# ADC.net
KiCad netlist of a schematic drawn in Altium Designer
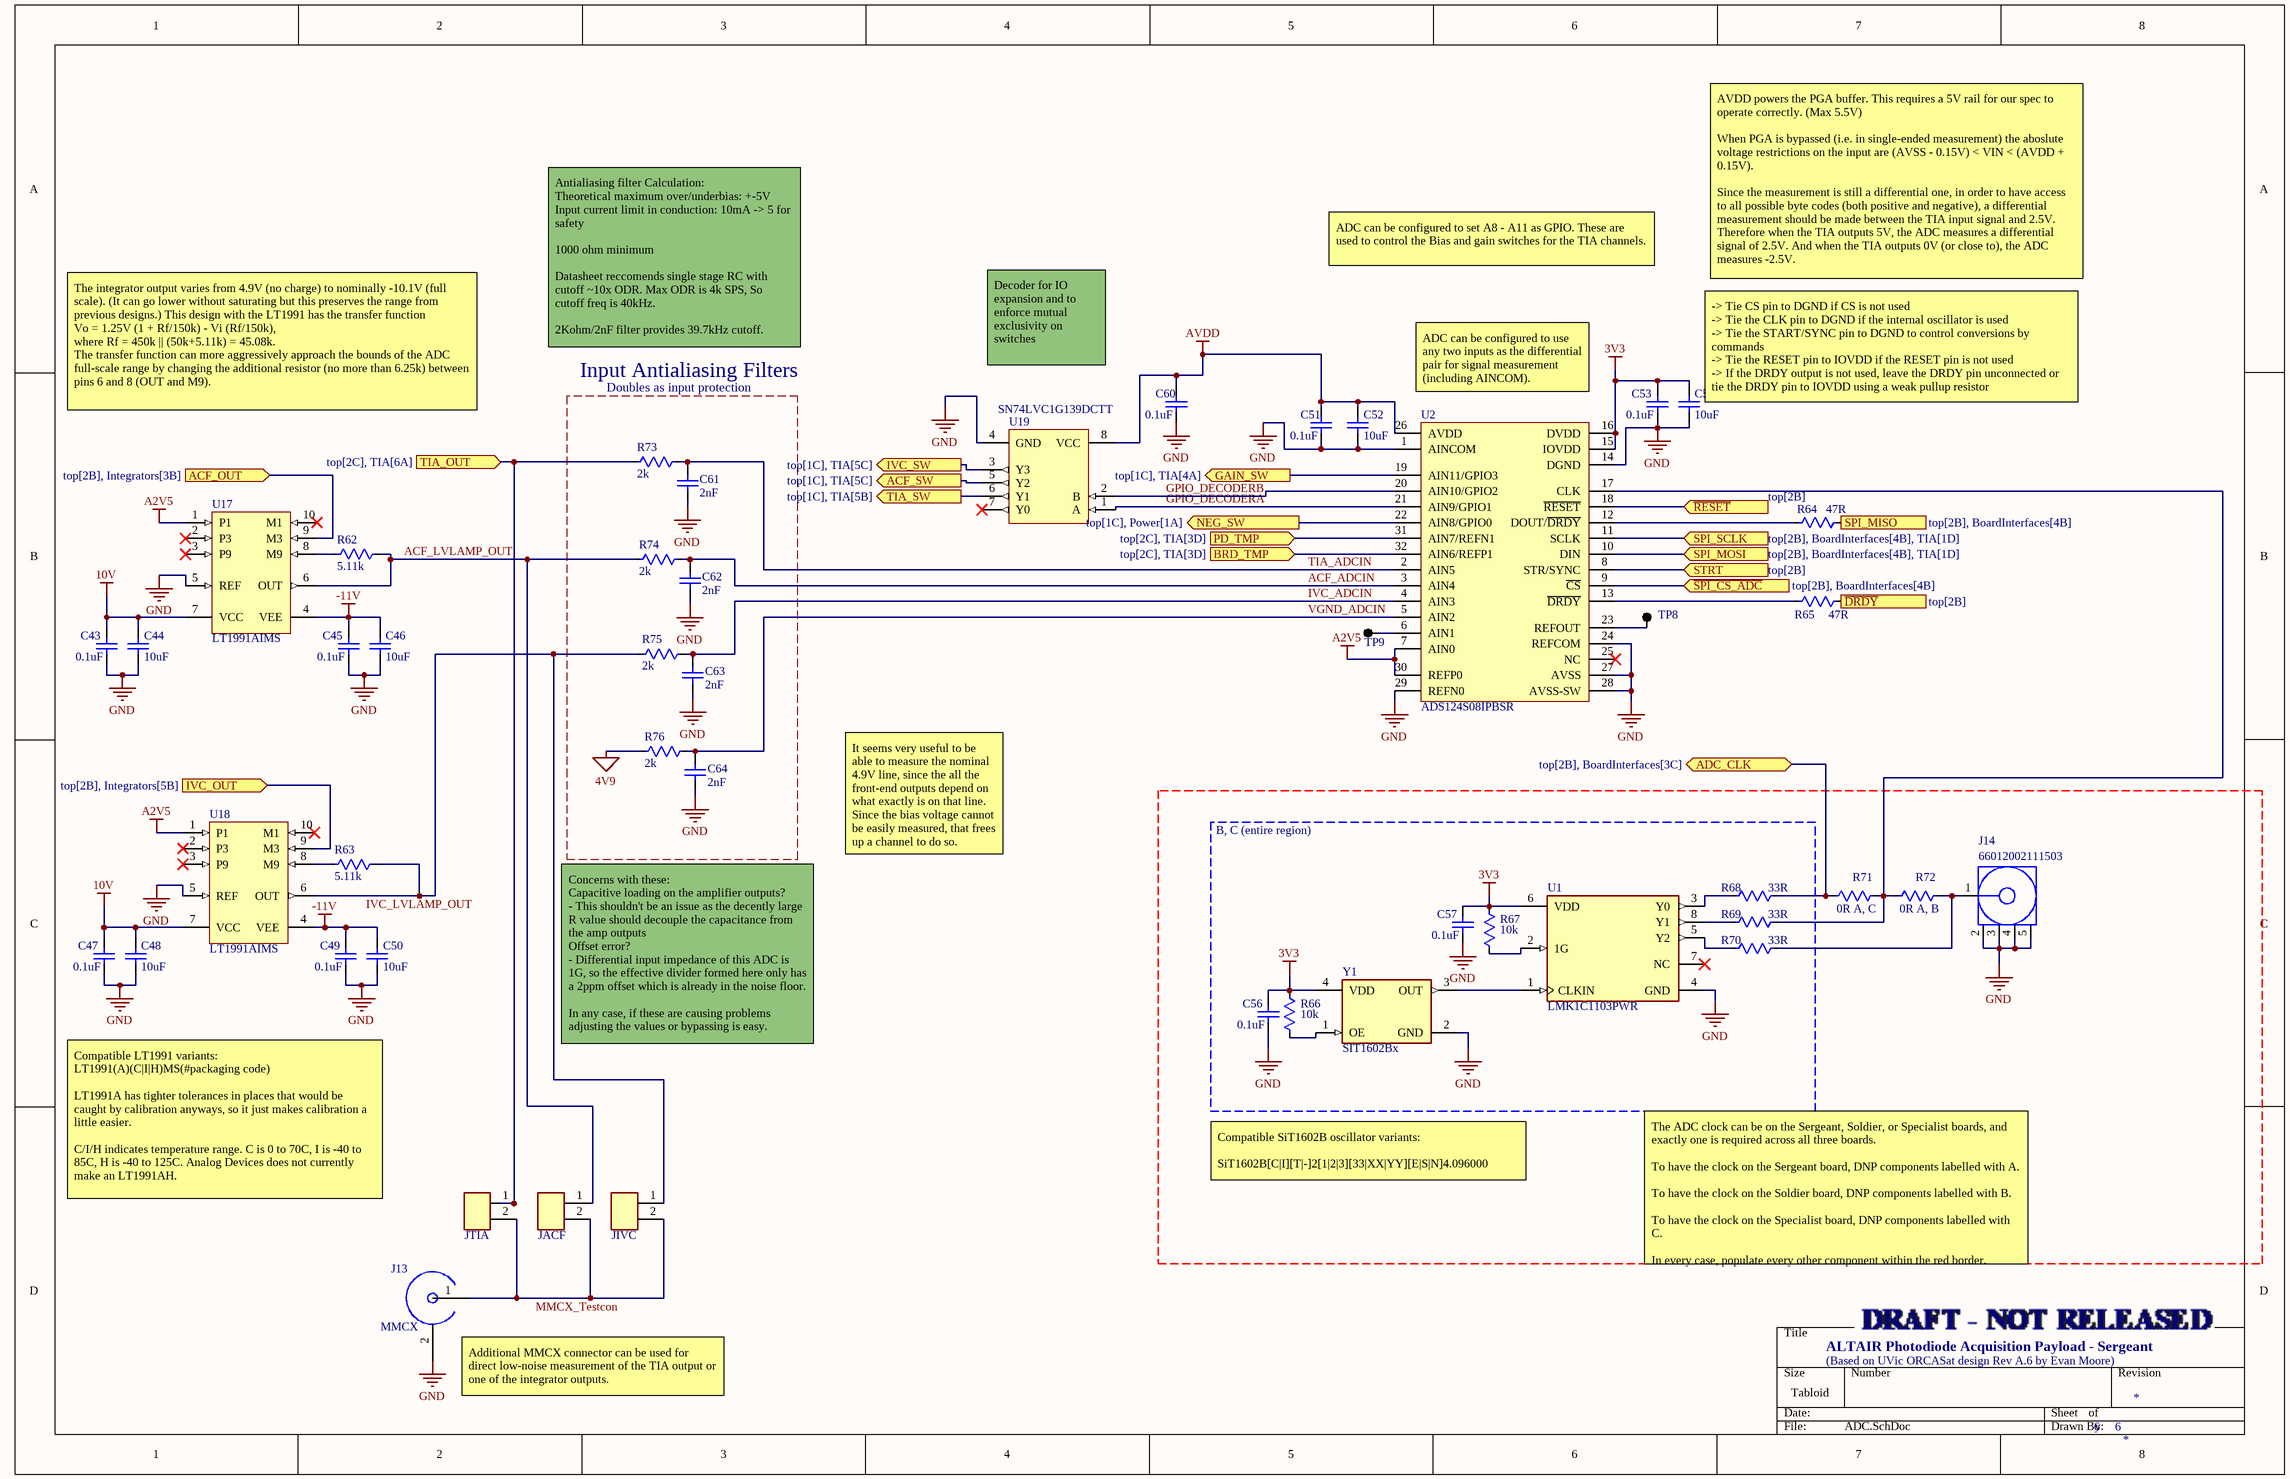
[diagram p0: ADC.SchDoc]

(export (version "E")
  (design (tool "Eeschema 10.0.6"))
  (components
    (comp (ref "C43")
      (value "0.1uF")
      (footprint "CAP 0603 NON-IPC KEMET X7R")
      (description "Kemet C0603C104K5RACAUTO - Cap Ceramic 0.1uF 50V X7R 10% 0603 125C Paper T/R")
      (fields (field (name "MF") "Kemet") (field (name "MP") "C0603C104K5RACAUTO"))
      (libsource (lib "ALTAIR_PD_Capacitors") (part "CAP"))
    )
    (comp (ref "C44")
      (value "10uF")
      (footprint "CAP 0805 IPC MID DENSITY")
      (description "Murata GRM21BR61E106KA73L - Cap Ceramic 10uF 10% 25V X5R 0805")
      (fields (field (name "MF") "Murata") (field (name "MP") "GRM21BR61E106KA73L"))
      (libsource (lib "ALTAIR_PD_Capacitors") (part "CAP"))
    )
    (comp (ref "C45")
      (value "0.1uF")
      (footprint "CAP 0603 NON-IPC KEMET X7R")
      (description "Kemet C0603C104K5RACAUTO - Cap Ceramic 0.1uF 50V X7R 10% 0603 125C Paper T/R")
      (fields (field (name "MF") "Kemet") (field (name "MP") "C0603C104K5RACAUTO"))
      (libsource (lib "ALTAIR_PD_Capacitors") (part "CAP"))
    )
    (comp (ref "C46")
      (value "10uF")
      (footprint "CAP 0805 IPC MID DENSITY")
      (description "Murata GRM21BR61E106KA73L - Cap Ceramic 10uF 10% 25V X5R 0805")
      (fields (field (name "MF") "Murata") (field (name "MP") "GRM21BR61E106KA73L"))
      (libsource (lib "ALTAIR_PD_Capacitors") (part "CAP"))
    )
    (comp (ref "C47")
      (value "0.1uF")
      (footprint "CAP 0603 NON-IPC KEMET X7R")
      (description "Kemet C0603C104K5RACAUTO - Cap Ceramic 0.1uF 50V X7R 10% 0603 125C Paper T/R")
      (fields (field (name "MF") "Kemet") (field (name "MP") "C0603C104K5RACAUTO"))
      (libsource (lib "ALTAIR_PD_Capacitors") (part "CAP"))
    )
    (comp (ref "C48")
      (value "10uF")
      (footprint "CAP 0805 IPC MID DENSITY")
      (description "Murata GRM21BR61E106KA73L - Cap Ceramic 10uF 10% 25V X5R 0805")
      (fields (field (name "MF") "Murata") (field (name "MP") "GRM21BR61E106KA73L"))
      (libsource (lib "ALTAIR_PD_Capacitors") (part "CAP"))
    )
    (comp (ref "C49")
      (value "0.1uF")
      (footprint "CAP 0603 NON-IPC KEMET X7R")
      (description "Kemet C0603C104K5RACAUTO - Cap Ceramic 0.1uF 50V X7R 10% 0603 125C Paper T/R")
      (fields (field (name "MF") "Kemet") (field (name "MP") "C0603C104K5RACAUTO"))
      (libsource (lib "ALTAIR_PD_Capacitors") (part "CAP"))
    )
    (comp (ref "C50")
      (value "10uF")
      (footprint "CAP 0805 IPC MID DENSITY")
      (description "Murata GRM21BR61E106KA73L - Cap Ceramic 10uF 10% 25V X5R 0805")
      (fields (field (name "MF") "Murata") (field (name "MP") "GRM21BR61E106KA73L"))
      (libsource (lib "ALTAIR_PD_Capacitors") (part "CAP"))
    )
    (comp (ref "C51")
      (value "0.1uF")
      (footprint "CAP 0603 IPC MID DENSITY")
      (description "Kemet C0603C104K5RACAUTO - Cap Ceramic 0.1uF 50V X7R 10% 0603 125C Paper T/R")
      (fields (field (name "MF") "Kemet") (field (name "MP") "C0603C104K5RACAUTO"))
      (libsource (lib "ALTAIR_PD_Capacitors") (part "CAP"))
    )
    (comp (ref "C52")
      (value "10uF")
      (footprint "CAP 0805 IPC MID DENSITY")
      (description "Murata GRM21BR61E106KA73L - Cap Ceramic 10uF 10% 25V X5R 0805")
      (fields (field (name "MF") "Murata") (field (name "MP") "GRM21BR61E106KA73L"))
      (libsource (lib "ALTAIR_PD_Capacitors") (part "CAP"))
    )
    (comp (ref "C53")
      (value "0.1uF")
      (footprint "CAP 0603 IPC MID DENSITY")
      (description "Kemet C0603C104K5RACAUTO - Cap Ceramic 0.1uF 50V X7R 10% 0603 125C Paper T/R")
      (fields (field (name "MF") "Kemet") (field (name "MP") "C0603C104K5RACAUTO"))
      (libsource (lib "ALTAIR_PD_Capacitors") (part "CAP"))
    )
    (comp (ref "C54")
      (value "10uF")
      (footprint "CAP 0805 IPC MID DENSITY")
      (description "Murata GRM21BR61E106KA73L - Cap Ceramic 10uF 10% 25V X5R 0805")
      (fields (field (name "MF") "Murata") (field (name "MP") "GRM21BR61E106KA73L"))
      (libsource (lib "ALTAIR_PD_Capacitors") (part "CAP"))
    )
    (comp (ref "C56")
      (value "0.1uF")
      (footprint "CAP 0603 IPC MID DENSITY")
      (description "Kemet C0603C104K5RACAUTO - Cap Ceramic 0.1uF 50V X7R 10% 0603 125C Paper T/R")
      (fields (field (name "MF") "Kemet") (field (name "MP") "C0603C104K5RACAUTO"))
      (libsource (lib "ALTAIR_PD_Capacitors") (part "CAP"))
    )
    (comp (ref "C57")
      (value "0.1uF")
      (footprint "CAP 0603 IPC MID DENSITY")
      (description "Kemet C0603C104K5RACAUTO - Cap Ceramic 0.1uF 50V X7R 10% 0603 125C Paper T/R")
      (fields (field (name "MF") "Kemet") (field (name "MP") "C0603C104K5RACAUTO"))
      (libsource (lib "ALTAIR_PD_Capacitors") (part "CAP"))
    )
    (comp (ref "C60")
      (value "0.1uF")
      (footprint "CAP 0603 IPC MID DENSITY")
      (description "Kemet C0603C104K5RACAUTO - Cap Ceramic 0.1uF 50V X7R 10% 0603 125C Paper T/R")
      (fields (field (name "MF") "Kemet") (field (name "MP") "C0603C104K5RACAUTO"))
      (libsource (lib "ALTAIR_PD_Capacitors") (part "CAP"))
    )
    (comp (ref "C61")
      (value "2nF")
      (footprint "CAP 0603 IPC MID DENSITY")
      (description "Cap, Nonpolar, Any, Must choose footprint manually")
      (libsource (lib "ALTAIR_PD_Capacitors") (part "CAP"))
    )
    (comp (ref "C62")
      (value "2nF")
      (footprint "CAP 0603 IPC MID DENSITY")
      (description "Cap, Nonpolar, Any, Must choose footprint manually")
      (libsource (lib "ALTAIR_PD_Capacitors") (part "CAP"))
    )
    (comp (ref "C63")
      (value "2nF")
      (footprint "CAP 0603 IPC MID DENSITY")
      (description "Cap, Nonpolar, Any, Must choose footprint manually")
      (libsource (lib "ALTAIR_PD_Capacitors") (part "CAP"))
    )
    (comp (ref "C64")
      (value "2nF")
      (footprint "CAP 0603 IPC MID DENSITY")
      (description "Cap, Nonpolar, Any, Must choose footprint manually")
      (libsource (lib "ALTAIR_PD_Capacitors") (part "CAP"))
    )
    (comp (ref "J13")
      (value "MMCX")
      (footprint "COAX MMCX SMD")
      (description "Conn MMCX F 50Ohm Solder ST SMD Gold Tray")
      (fields (field (name "MF") "Molex") (field (name "MP") "0734152061"))
      (libsource (lib "ALTAIR_PD_Coaxial") (part "MMCX_recp"))
    )
    (comp (ref "J14")
      (value "66012002111503")
      (footprint "COAX MMCX THT")
      (description "Rf Coaxial, Mmcx Jack, 50 Ohm, Pcb Rohs Compliant: Yes ¦Wurth Elektronik 66012002111503")
      (fields (field (name "MF") "Wurth Elektronik"))
      (libsource (lib "ALTAIR_PD_Coaxial") (part "CMP-207975-000001-3"))
    )
    (comp (ref "JACF")
      (value "JACF")
      (footprint "ALTAIR_PD_Headers:JUMPER 2POS 1MM PITCH THT")
      (description "2x1 Header THT 1mm Pitch")
      (fields
        (field (name "MF") "GCT (GLOBAL CONNECTOR TECHNOLOGY)")
        (field (name "MP") "BC020-02-A-0200-0300-L-G")
      )
      (libsource (lib "ALTAIR_PD_Headers") (part "BC020-02-A-0200-0300-L-G"))
    )
    (comp (ref "JIVC")
      (value "JIVC")
      (footprint "ALTAIR_PD_Headers:JUMPER 2POS 1MM PITCH THT")
      (description "2x1 Header THT 1mm Pitch")
      (fields
        (field (name "MF") "GCT (GLOBAL CONNECTOR TECHNOLOGY)")
        (field (name "MP") "BC020-02-A-0200-0300-L-G")
      )
      (libsource (lib "ALTAIR_PD_Headers") (part "BC020-02-A-0200-0300-L-G"))
    )
    (comp (ref "JTIA")
      (value "JTIA")
      (footprint "ALTAIR_PD_Headers:JUMPER 2POS 1MM PITCH THT")
      (description "2x1 Header THT 1mm Pitch")
      (fields
        (field (name "MF") "GCT (GLOBAL CONNECTOR TECHNOLOGY)")
        (field (name "MP") "BC020-02-A-0200-0300-L-G")
      )
      (libsource (lib "ALTAIR_PD_Headers") (part "BC020-02-A-0200-0300-L-G"))
    )
    (comp (ref "R62")
      (value "5.11k")
      (footprint "RES 0402 IPC MID DENSITY")
      (description "Panasonic ERA-2AEB5111X - Res 5.11k 0.1% 1/16W SMD 0402")
      (fields (field (name "MF") "Panasonic Electronic Components") (field (name "MP") "ERA-2AEB5111X"))
      (libsource (lib "ALTAIR_PD_Resistors") (part "RES"))
    )
    (comp (ref "R63")
      (value "5.11k")
      (footprint "RES 0402 IPC MID DENSITY")
      (description "Panasonic ERA-2AEB5111X - Res 5.11k 0.1% 1/16W SMD 0402")
      (fields (field (name "MF") "Panasonic Electronic Components") (field (name "MP") "ERA-2AEB5111X"))
      (libsource (lib "ALTAIR_PD_Resistors") (part "RES"))
    )
    (comp (ref "R64")
      (value "47R")
      (footprint "RES 0402 NON-IPC SEI")
      (description "Stackpole RMCF0402JT47R0 - Res 47Ohm 5% 0.063W 0402 Thick Film AEC-Q200 compliant")
      (fields (field (name "MF") "Stackpole Electronics Inc.") (field (name "MP") "RMCF0402JT47R0"))
      (libsource (lib "ALTAIR_PD_Resistors") (part "RES"))
    )
    (comp (ref "R65")
      (value "47R")
      (footprint "RES 0402 NON-IPC SEI")
      (description "Stackpole RMCF0402JT47R0 - Res 47Ohm 5% 0.063W 0402 Thick Film AEC-Q200 compliant")
      (fields (field (name "MF") "Stackpole Electronics Inc.") (field (name "MP") "RMCF0402JT47R0"))
      (libsource (lib "ALTAIR_PD_Resistors") (part "RES"))
    )
    (comp (ref "R66")
      (value "10k")
      (footprint "RES 0603 IPC MID DENSITY")
      (description "Vishay CRCW060310K0FKEA SMD 0603 10k, CRCW e3 Series, 75V, thick film, 100mW")
      (fields (field (name "MF") "Vishay Dale") (field (name "MP") "CRCW060310K0FKEA"))
      (libsource (lib "ALTAIR_PD_Resistors") (part "RES"))
    )
    (comp (ref "R67")
      (value "10k")
      (footprint "RES 0603 IPC MID DENSITY")
      (description "Vishay CRCW060310K0FKEA SMD 0603 10k, CRCW e3 Series, 75V, thick film, 100mW")
      (fields (field (name "MF") "Vishay Dale") (field (name "MP") "CRCW060310K0FKEA"))
      (libsource (lib "ALTAIR_PD_Resistors") (part "RES"))
    )
    (comp (ref "R68")
      (value "33R")
      (footprint "RES 0402 NON-IPC YAGEO")
      (description "Yageo RC0402FR-0733RL - Res 33Ohm 1% 1/16W 0402")
      (fields (field (name "MF") "YAGEO") (field (name "MP") "RC0402FR-0733RL"))
      (libsource (lib "ALTAIR_PD_Resistors") (part "RES"))
    )
    (comp (ref "R69")
      (value "33R")
      (footprint "RES 0402 NON-IPC YAGEO")
      (description "Yageo RC0402FR-0733RL - Res 33Ohm 1% 1/16W 0402")
      (fields (field (name "MF") "YAGEO") (field (name "MP") "RC0402FR-0733RL"))
      (libsource (lib "ALTAIR_PD_Resistors") (part "RES"))
    )
    (comp (ref "R70")
      (value "33R")
      (footprint "RES 0402 NON-IPC YAGEO")
      (description "Yageo RC0402FR-0733RL - Res 33Ohm 1% 1/16W 0402")
      (fields (field (name "MF") "YAGEO") (field (name "MP") "RC0402FR-0733RL"))
      (libsource (lib "ALTAIR_PD_Resistors") (part "RES"))
    )
    (comp (ref "R71")
      (value "0R A, C")
      (footprint "RES 0402 IPC MID DENSITY")
      (description "Yageo RC0402JR-070RL - Res 0 Ohms 1/16W SMD 0402")
      (fields (field (name "MF") "YAGEO") (field (name "MP") "RC0402JR-070RL"))
      (libsource (lib "ALTAIR_PD_Resistors") (part "RES"))
    )
    (comp (ref "R72")
      (value "0R A, B")
      (footprint "RES 0402 IPC MID DENSITY")
      (description "Yageo RC0402JR-070RL - Res 0 Ohms 1/16W SMD 0402")
      (fields (field (name "MF") "YAGEO") (field (name "MP") "RC0402JR-070RL"))
      (libsource (lib "ALTAIR_PD_Resistors") (part "RES"))
    )
    (comp (ref "R73")
      (value "2k")
      (footprint "RES 0603 IPC MID DENSITY")
      (description "Res, Any, Manually select footprint")
      (libsource (lib "ALTAIR_PD_Resistors") (part "RES"))
    )
    (comp (ref "R74")
      (value "2k")
      (footprint "RES 0603 IPC MID DENSITY")
      (description "Res, Any, Manually select footprint")
      (libsource (lib "ALTAIR_PD_Resistors") (part "RES"))
    )
    (comp (ref "R75")
      (value "2k")
      (footprint "RES 0603 IPC MID DENSITY")
      (description "Res, Any, Manually select footprint")
      (libsource (lib "ALTAIR_PD_Resistors") (part "RES"))
    )
    (comp (ref "R76")
      (value "2k")
      (footprint "RES 0603 IPC MID DENSITY")
      (description "Res, Any, Manually select footprint")
      (libsource (lib "ALTAIR_PD_Resistors") (part "RES"))
    )
    (comp (ref "TP8")
      (value "Testpoint")
      (footprint "TESTPOINT THT")
      (libsource (lib "ALTAIR_PD_Testpoint") (part "Testpoint"))
    )
    (comp (ref "TP9")
      (value "Testpoint")
      (footprint "TESTPOINT THT")
      (libsource (lib "ALTAIR_PD_Testpoint") (part "Testpoint"))
    )
    (comp (ref "U1")
      (value "LMK1C1103PWR")
      (footprint "8-TSSOP 0.65MM PITCH 4.4MM WIDTH IPC MID DENSITY")
      (description "LVCMOS CLOCK BUFFER 3-CHANNEL")
      (fields (field (name "MF") "Texas Instruments"))
      (libsource (lib "ALTAIR_PD_ClockParts") (part "LMK1C1103PWR"))
    )
    (comp (ref "U2")
      (value "ADS124S08IPBSR")
      (footprint "32TQFP 7X7MM IPC LOW DENSITY")
      (description "24BIT ADC Delta-Sigma 4k samples/s PGA V-reference")
      (fields (field (name "MF") "Texas Instruments"))
      (libsource (lib "ALTAIR_PD_ADCs") (part "ADS124S08IPBSR"))
    )
    (comp (ref "U17")
      (value "LT1991AIMS")
      (footprint "10-SOP 0.5MM PITCH 3MM WIDTH IPC HIGH DENSITY")
      (fields
        (field (name "MF") "Linear Technology")
        (field (name "MP") "LT1991AIMS#PBF")
        (field (name "LINEAR TECHNOLOGY PART NUMBER") "LT1991")
      )
      (libsource (lib "ALTAIR_PD_Amplifiers") (part "LT1991IMS#TRPBF"))
    )
    (comp (ref "U18")
      (value "LT1991AIMS")
      (footprint "10-SOP 0.5MM PITCH 3MM WIDTH IPC HIGH DENSITY")
      (fields
        (field (name "MF") "Linear Technology")
        (field (name "MP") "LT1991AIMS#PBF")
        (field (name "LINEAR TECHNOLOGY PART NUMBER") "LT1991")
      )
      (libsource (lib "ALTAIR_PD_Amplifiers") (part "LT1991IMS#TRPBF"))
    )
    (comp (ref "U19")
      (value "SN74LVC1G139DCTT")
      (footprint "DCT0008A_L")
      (description "2-Line-to-4-Line Decoder, DCT0008A, SMALL T&R")
      (fields
        (field (name "MANUFACTURER") "Texas Instruments")
        (field (name "GENERIC PART NUMBER") "SN74LVC1G139")
      )
      (libsource (lib "Altium Content Vault") (part "TI-SN74LVC1G139-8"))
    )
    (comp (ref "Y1")
      (value "SIT1602Bx")
      (footprint "4PQFN NON-IPC SITIME")
      (description "MEMS OSC XO 4.096MHZ H/LVCMOS")
      (fields (field (name "MF") "SiTime") (field (name "MP") "SiT1602BC-21-XXN-4.096000"))
      (libsource (lib "ALTAIR_PD_ClockParts") (part "SIT1602Bx"))
    )
  )
  (nets
    (net (code "1") (name "-11V") (class "Default")
      (node (ref "C45") (pin "2") (pinfunction "2_2") (pintype "passive"))
      (node (ref "C46") (pin "2") (pinfunction "2_2") (pintype "passive"))
      (node (ref "C49") (pin "2") (pinfunction "2_2") (pintype "passive"))
      (node (ref "C50") (pin "2") (pinfunction "2_2") (pintype "passive"))
      (node (ref "U17") (pin "4") (pinfunction "VEE_4") (pintype "power_in"))
      (node (ref "U18") (pin "4") (pinfunction "VEE_4") (pintype "power_in"))
    )
    (net (code "2") (name "/ACF_ADCIN") (class "Default")
      (node (ref "C62") (pin "2") (pinfunction "2_2") (pintype "passive"))
      (node (ref "R74") (pin "2") (pinfunction "2_2") (pintype "passive"))
      (node (ref "U2") (pin "3") (pinfunction "AIN4_3") (pintype "passive"))
    )
    (net (code "3") (name "/ACF_LVLAMP_OUT") (class "Default")
      (node (ref "JACF") (pin "1") (pinfunction "1_1") (pintype "passive"))
      (node (ref "R62") (pin "2") (pinfunction "2_2") (pintype "passive"))
      (node (ref "R74") (pin "1") (pinfunction "1_1") (pintype "passive"))
      (node (ref "U17") (pin "6") (pinfunction "OUT_6") (pintype "output"))
    )
    (net (code "4") (name "/ACF_OUT") (class "Default")
      (node (ref "U17") (pin "9") (pinfunction "M3_9") (pintype "input"))
    )
    (net (code "5") (name "/ACF_SW") (class "Default")
      (node (ref "U19") (pin "5") (pinfunction "Y2_5") (pintype "output"))
    )
    (net (code "6") (name "/ADC_CLK") (class "Default")
      (node (ref "R68") (pin "1") (pinfunction "1_1") (pintype "passive"))
      (node (ref "R71") (pin "2") (pinfunction "2_2") (pintype "passive"))
    )
    (net (code "7") (name "/BRD_TMP") (class "Default")
      (node (ref "U2") (pin "32") (pinfunction "AIN6/REFP1_32") (pintype "passive"))
    )
    (net (code "8") (name "/DRDY") (class "Default")
      (node (ref "R65") (pin "2") (pinfunction "2_2") (pintype "passive"))
    )
    (net (code "9") (name "/GAIN_SW") (class "Default")
      (node (ref "U2") (pin "19") (pinfunction "AIN11/GPIO3_19") (pintype "passive"))
    )
    (net (code "10") (name "/GPIO_DECODERA") (class "Default")
      (node (ref "U19") (pin "1") (pinfunction "A_1") (pintype "input"))
      (node (ref "U2") (pin "21") (pinfunction "AIN9/GPIO1_21") (pintype "passive"))
    )
    (net (code "11") (name "/GPIO_DECODERB") (class "Default")
      (node (ref "U19") (pin "2") (pinfunction "B_2") (pintype "input"))
      (node (ref "U2") (pin "20") (pinfunction "AIN10/GPIO2_20") (pintype "passive"))
    )
    (net (code "12") (name "/IVC_ADCIN") (class "Default")
      (node (ref "C63") (pin "2") (pinfunction "2_2") (pintype "passive"))
      (node (ref "R75") (pin "2") (pinfunction "2_2") (pintype "passive"))
      (node (ref "U2") (pin "4") (pinfunction "AIN3_4") (pintype "passive"))
    )
    (net (code "13") (name "/IVC_LVLAMP_OUT") (class "Default")
      (node (ref "JIVC") (pin "1") (pinfunction "1_1") (pintype "passive"))
      (node (ref "R63") (pin "2") (pinfunction "2_2") (pintype "passive"))
      (node (ref "R75") (pin "1") (pinfunction "1_1") (pintype "passive"))
      (node (ref "U18") (pin "6") (pinfunction "OUT_6") (pintype "output"))
    )
    (net (code "14") (name "/IVC_OUT") (class "Default")
      (node (ref "U18") (pin "9") (pinfunction "M3_9") (pintype "input"))
    )
    (net (code "15") (name "/IVC_SW") (class "Default")
      (node (ref "U19") (pin "3") (pinfunction "Y3_3") (pintype "output"))
    )
    (net (code "16") (name "/MMCX_Testcon") (class "Default")
      (node (ref "J13") (pin "1") (pinfunction "1_1") (pintype "passive"))
      (node (ref "JACF") (pin "2") (pinfunction "2_2") (pintype "passive"))
      (node (ref "JIVC") (pin "2") (pinfunction "2_2") (pintype "passive"))
      (node (ref "JTIA") (pin "2") (pinfunction "2_2") (pintype "passive"))
    )
    (net (code "17") (name "/NEG_SW") (class "Default")
      (node (ref "U2") (pin "22") (pinfunction "AIN8/GPIO0_22") (pintype "passive"))
    )
    (net (code "18") (name "/PD_TMP") (class "Default")
      (node (ref "U2") (pin "31") (pinfunction "AIN7/REFN1_31") (pintype "passive"))
    )
    (net (code "19") (name "/RESET") (class "Default")
      (node (ref "U2") (pin "18") (pinfunction "~{RESET}_18") (pintype "passive"))
    )
    (net (code "20") (name "/SPI_CS_ADC") (class "Default")
      (node (ref "U2") (pin "9") (pinfunction "~{CS}_9") (pintype "passive"))
    )
    (net (code "21") (name "/SPI_MISO") (class "Default")
      (node (ref "R64") (pin "2") (pinfunction "2_2") (pintype "passive"))
    )
    (net (code "22") (name "/SPI_MOSI") (class "Default")
      (node (ref "U2") (pin "10") (pinfunction "DIN_10") (pintype "passive"))
    )
    (net (code "23") (name "/SPI_SCLK") (class "Default")
      (node (ref "U2") (pin "11") (pinfunction "SCLK_11") (pintype "passive"))
    )
    (net (code "24") (name "/STRT") (class "Default")
      (node (ref "U2") (pin "8") (pinfunction "STR/SYNC_8") (pintype "passive"))
    )
    (net (code "25") (name "/TIA_ADCIN") (class "Default")
      (node (ref "C61") (pin "2") (pinfunction "2_2") (pintype "passive"))
      (node (ref "R73") (pin "2") (pinfunction "2_2") (pintype "passive"))
      (node (ref "U2") (pin "2") (pinfunction "AIN5_2") (pintype "passive"))
    )
    (net (code "26") (name "/TIA_OUT") (class "Default")
      (node (ref "JTIA") (pin "1") (pinfunction "1_1") (pintype "passive"))
      (node (ref "R73") (pin "1") (pinfunction "1_1") (pintype "passive"))
    )
    (net (code "27") (name "/TIA_SW") (class "Default")
      (node (ref "U19") (pin "6") (pinfunction "Y1_6") (pintype "output"))
    )
    (net (code "28") (name "/VGND_ADCIN") (class "Default")
      (node (ref "C64") (pin "2") (pinfunction "2_2") (pintype "passive"))
      (node (ref "R76") (pin "2") (pinfunction "2_2") (pintype "passive"))
      (node (ref "U2") (pin "5") (pinfunction "AIN2_5") (pintype "passive"))
    )
    (net (code "29") (name "3V3") (class "Default")
      (node (ref "C53") (pin "2") (pinfunction "2_2") (pintype "passive"))
      (node (ref "C54") (pin "2") (pinfunction "2_2") (pintype "passive"))
      (node (ref "C56") (pin "2") (pinfunction "2_2") (pintype "passive"))
      (node (ref "C57") (pin "2") (pinfunction "2_2") (pintype "passive"))
      (node (ref "R66") (pin "2") (pinfunction "2_2") (pintype "passive"))
      (node (ref "R67") (pin "2") (pinfunction "2_2") (pintype "passive"))
      (node (ref "U1") (pin "6") (pinfunction "VDD_6") (pintype "power_in"))
      (node (ref "U2") (pin "15") (pinfunction "IOVDD_15") (pintype "passive"))
      (node (ref "U2") (pin "16") (pinfunction "DVDD_16") (pintype "passive"))
      (node (ref "Y1") (pin "4") (pinfunction "VDD_4") (pintype "power_in"))
    )
    (net (code "30") (name "4V9") (class "Default")
      (node (ref "R76") (pin "1") (pinfunction "1_1") (pintype "passive"))
    )
    (net (code "31") (name "10V") (class "Default")
      (node (ref "C43") (pin "2") (pinfunction "2_2") (pintype "passive"))
      (node (ref "C44") (pin "2") (pinfunction "2_2") (pintype "passive"))
      (node (ref "C47") (pin "2") (pinfunction "2_2") (pintype "passive"))
      (node (ref "C48") (pin "2") (pinfunction "2_2") (pintype "passive"))
      (node (ref "U17") (pin "7") (pinfunction "VCC_7") (pintype "power_in"))
      (node (ref "U18") (pin "7") (pinfunction "VCC_7") (pintype "power_in"))
    )
    (net (code "32") (name "A2V5") (class "Default")
      (node (ref "U17") (pin "1") (pinfunction "P1_1") (pintype "input"))
      (node (ref "U18") (pin "1") (pinfunction "P1_1") (pintype "input"))
      (node (ref "U2") (pin "30") (pinfunction "REFP0_30") (pintype "passive"))
      (node (ref "U2") (pin "7") (pinfunction "AIN0_7") (pintype "passive"))
    )
    (net (code "33") (name "AVDD") (class "Default")
      (node (ref "C51") (pin "2") (pinfunction "2_2") (pintype "passive"))
      (node (ref "C52") (pin "2") (pinfunction "2_2") (pintype "passive"))
      (node (ref "C60") (pin "2") (pinfunction "2_2") (pintype "passive"))
      (node (ref "U19") (pin "8") (pinfunction "VCC_8") (pintype "power_in"))
      (node (ref "U2") (pin "26") (pinfunction "AVDD_26") (pintype "passive"))
    )
    (net (code "34") (name "GND") (class "Default")
      (node (ref "C43") (pin "1") (pinfunction "1_1") (pintype "passive"))
      (node (ref "C44") (pin "1") (pinfunction "1_1") (pintype "passive"))
      (node (ref "C45") (pin "1") (pinfunction "1_1") (pintype "passive"))
      (node (ref "C46") (pin "1") (pinfunction "1_1") (pintype "passive"))
      (node (ref "C47") (pin "1") (pinfunction "1_1") (pintype "passive"))
      (node (ref "C48") (pin "1") (pinfunction "1_1") (pintype "passive"))
      (node (ref "C49") (pin "1") (pinfunction "1_1") (pintype "passive"))
      (node (ref "C50") (pin "1") (pinfunction "1_1") (pintype "passive"))
      (node (ref "C51") (pin "1") (pinfunction "1_1") (pintype "passive"))
      (node (ref "C52") (pin "1") (pinfunction "1_1") (pintype "passive"))
      (node (ref "C53") (pin "1") (pinfunction "1_1") (pintype "passive"))
      (node (ref "C54") (pin "1") (pinfunction "1_1") (pintype "passive"))
      (node (ref "C56") (pin "1") (pinfunction "1_1") (pintype "passive"))
      (node (ref "C57") (pin "1") (pinfunction "1_1") (pintype "passive"))
      (node (ref "C60") (pin "1") (pinfunction "1_1") (pintype "passive"))
      (node (ref "C61") (pin "1") (pinfunction "1_1") (pintype "passive"))
      (node (ref "C62") (pin "1") (pinfunction "1_1") (pintype "passive"))
      (node (ref "C63") (pin "1") (pinfunction "1_1") (pintype "passive"))
      (node (ref "C64") (pin "1") (pinfunction "1_1") (pintype "passive"))
      (node (ref "J13") (pin "2") (pinfunction "2_2") (pintype "passive"))
      (node (ref "J14") (pin "2") (pinfunction "GND_2") (pintype "passive"))
      (node (ref "J14") (pin "3") (pinfunction "GND_3") (pintype "passive"))
      (node (ref "J14") (pin "4") (pinfunction "GND_4") (pintype "passive"))
      (node (ref "J14") (pin "5") (pinfunction "GND_5") (pintype "passive"))
      (node (ref "U1") (pin "4") (pinfunction "GND_4") (pintype "power_in"))
      (node (ref "U17") (pin "5") (pinfunction "REF_5") (pintype "input"))
      (node (ref "U18") (pin "5") (pinfunction "REF_5") (pintype "input"))
      (node (ref "U19") (pin "4") (pinfunction "GND_4") (pintype "power_in"))
      (node (ref "U2") (pin "1") (pinfunction "AINCOM_1") (pintype "passive"))
      (node (ref "U2") (pin "14") (pinfunction "DGND_14") (pintype "passive"))
      (node (ref "U2") (pin "24") (pinfunction "REFCOM_24") (pintype "passive"))
      (node (ref "U2") (pin "27") (pinfunction "AVSS_27") (pintype "passive"))
      (node (ref "U2") (pin "28") (pinfunction "AVSS-SW_28") (pintype "passive"))
      (node (ref "U2") (pin "29") (pinfunction "REFN0_29") (pintype "passive"))
      (node (ref "Y1") (pin "2") (pinfunction "GND_2") (pintype "power_in"))
    )
    (net (code "35") (name "Net-(J14-Signal)") (class "Default")
      (node (ref "J14") (pin "1") (pinfunction "Signal_1") (pintype "passive"))
      (node (ref "R70") (pin "1") (pinfunction "1_1") (pintype "passive"))
      (node (ref "R72") (pin "1") (pinfunction "1_1") (pintype "passive"))
    )
    (net (code "36") (name "Net-(U1-1G)") (class "Default")
      (node (ref "R67") (pin "1") (pinfunction "1_1") (pintype "passive"))
      (node (ref "U1") (pin "2") (pinfunction "1G_2") (pintype "input"))
    )
    (net (code "37") (name "Net-(U1-CLKIN)") (class "Default")
      (node (ref "U1") (pin "1") (pinfunction "CLKIN_1") (pintype "input"))
      (node (ref "Y1") (pin "3") (pinfunction "OUT_3") (pintype "output"))
    )
    (net (code "38") (name "Net-(U1-Y0)") (class "Default")
      (node (ref "R68") (pin "2") (pinfunction "2_2") (pintype "passive"))
      (node (ref "U1") (pin "3") (pinfunction "Y0_3") (pintype "output"))
    )
    (net (code "39") (name "Net-(U1-Y1)") (class "Default")
      (node (ref "R69") (pin "2") (pinfunction "2_2") (pintype "passive"))
      (node (ref "U1") (pin "8") (pinfunction "Y1_8") (pintype "output"))
    )
    (net (code "40") (name "Net-(U1-Y2)") (class "Default")
      (node (ref "R70") (pin "2") (pinfunction "2_2") (pintype "passive"))
      (node (ref "U1") (pin "5") (pinfunction "Y2_5") (pintype "output"))
    )
    (net (code "41") (name "Net-(U2-AIN1)") (class "Default")
      (node (ref "TP9") (pin "1") (pinfunction "1_1") (pintype "passive"))
      (node (ref "U2") (pin "6") (pinfunction "AIN1_6") (pintype "passive"))
    )
    (net (code "42") (name "Net-(U2-CLK)") (class "Default")
      (node (ref "R69") (pin "1") (pinfunction "1_1") (pintype "passive"))
      (node (ref "R71") (pin "1") (pinfunction "1_1") (pintype "passive"))
      (node (ref "R72") (pin "2") (pinfunction "2_2") (pintype "passive"))
      (node (ref "U2") (pin "17") (pinfunction "CLK_17") (pintype "passive"))
    )
    (net (code "43") (name "Net-(U2-DOUT{slash}~{DRDY})") (class "Default")
      (node (ref "R64") (pin "1") (pinfunction "1_1") (pintype "passive"))
      (node (ref "U2") (pin "12") (pinfunction "DOUT/~{DRDY}_12") (pintype "passive"))
    )
    (net (code "44") (name "Net-(U2-REFOUT)") (class "Default")
      (node (ref "TP8") (pin "1") (pinfunction "1_1") (pintype "passive"))
      (node (ref "U2") (pin "23") (pinfunction "REFOUT_23") (pintype "passive"))
    )
    (net (code "45") (name "Net-(U2-~{DRDY})") (class "Default")
      (node (ref "R65") (pin "1") (pinfunction "1_1") (pintype "passive"))
      (node (ref "U2") (pin "13") (pinfunction "~{DRDY}_13") (pintype "passive"))
    )
    (net (code "46") (name "Net-(U17-M9)") (class "Default")
      (node (ref "R62") (pin "1") (pinfunction "1_1") (pintype "passive"))
      (node (ref "U17") (pin "8") (pinfunction "M9_8") (pintype "input"))
    )
    (net (code "47") (name "Net-(U18-M9)") (class "Default")
      (node (ref "R63") (pin "1") (pinfunction "1_1") (pintype "passive"))
      (node (ref "U18") (pin "8") (pinfunction "M9_8") (pintype "input"))
    )
    (net (code "48") (name "Net-(Y1-OE)") (class "Default")
      (node (ref "R66") (pin "1") (pinfunction "1_1") (pintype "passive"))
      (node (ref "Y1") (pin "1") (pinfunction "OE_1") (pintype "input"))
    )
    (net (code "49") (name "unconnected-(U1-NC-Pad7)") (class "Default")
      (node (ref "U1") (pin "7") (pinfunction "NC_7") (pintype "passive+no_connect"))
    )
    (net (code "50") (name "unconnected-(U2-NC-Pad25)") (class "Default")
      (node (ref "U2") (pin "25") (pinfunction "NC_25") (pintype "passive+no_connect"))
    )
    (net (code "51") (name "unconnected-(U17-M1-Pad10)") (class "Default")
      (node (ref "U17") (pin "10") (pinfunction "M1_10") (pintype "input+no_connect"))
    )
    (net (code "52") (name "unconnected-(U17-P3-Pad2)") (class "Default")
      (node (ref "U17") (pin "2") (pinfunction "P3_2") (pintype "input+no_connect"))
    )
    (net (code "53") (name "unconnected-(U17-P9-Pad3)") (class "Default")
      (node (ref "U17") (pin "3") (pinfunction "P9_3") (pintype "input+no_connect"))
    )
    (net (code "54") (name "unconnected-(U18-M1-Pad10)") (class "Default")
      (node (ref "U18") (pin "10") (pinfunction "M1_10") (pintype "input+no_connect"))
    )
    (net (code "55") (name "unconnected-(U18-P3-Pad2)") (class "Default")
      (node (ref "U18") (pin "2") (pinfunction "P3_2") (pintype "input+no_connect"))
    )
    (net (code "56") (name "unconnected-(U18-P9-Pad3)") (class "Default")
      (node (ref "U18") (pin "3") (pinfunction "P9_3") (pintype "input+no_connect"))
    )
    (net (code "57") (name "unconnected-(U19-Y0-Pad7)") (class "Default")
      (node (ref "U19") (pin "7") (pinfunction "Y0_7") (pintype "output+no_connect"))
    )
  )
)
